# b291_rev0.net
KiCad netlist of a schematic drawn in EAGLE
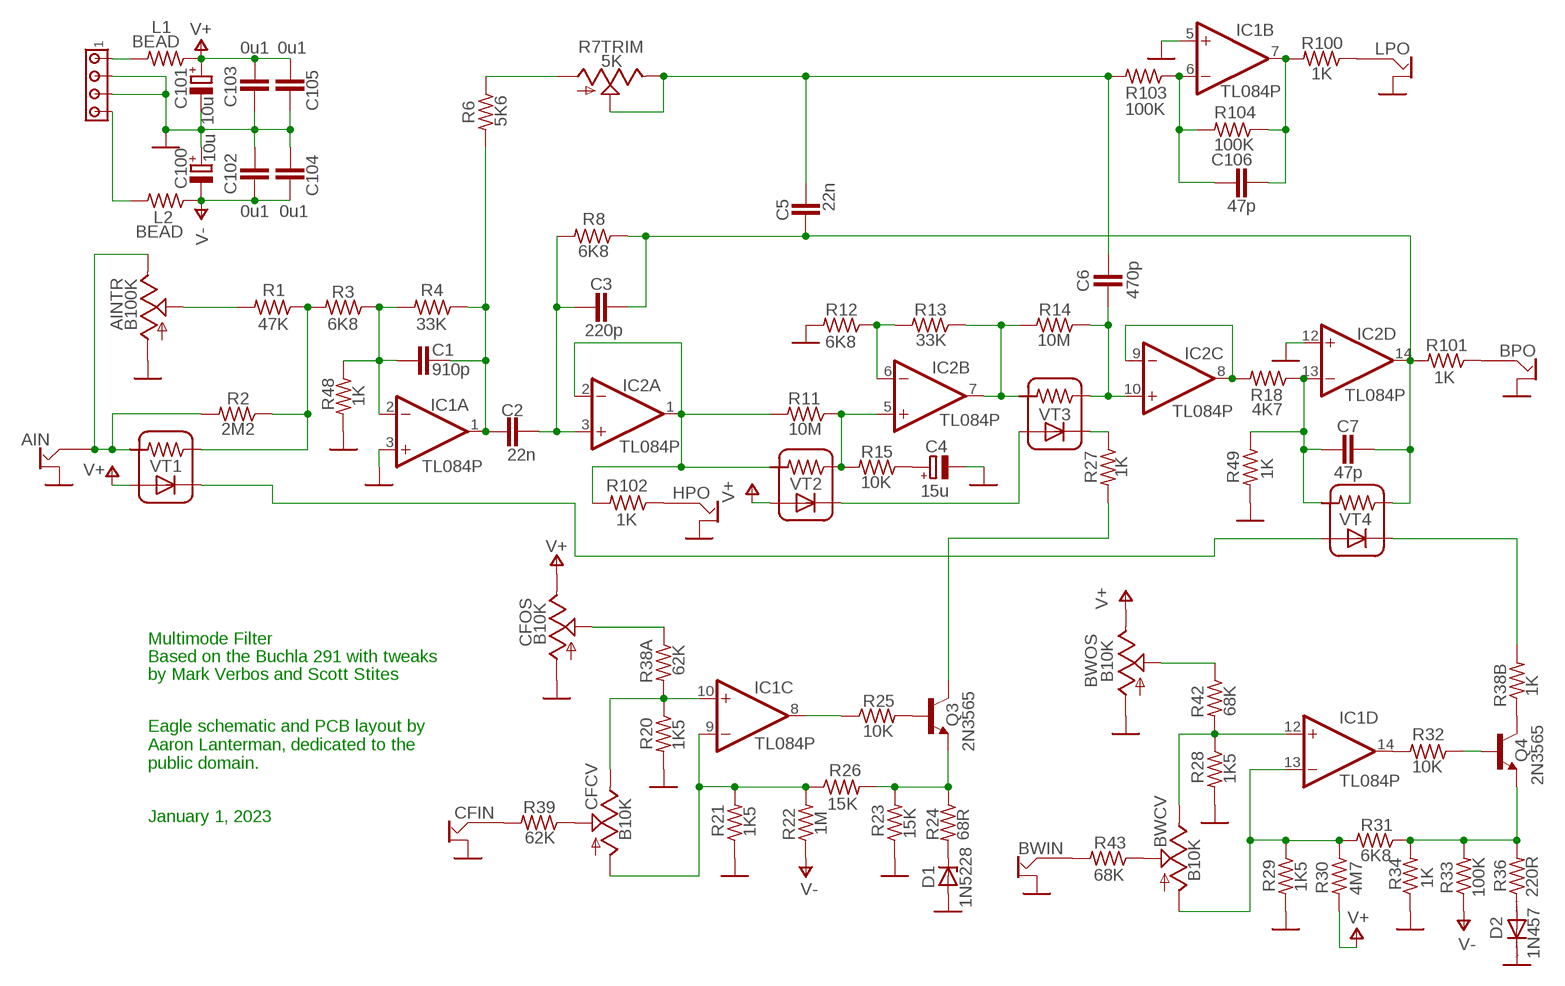
[diagram p0: schematic, sheet 1]

(export (version "E")
  (design (tool "Eeschema 10.0.6"))
  (components
    (comp (ref "AIN")
      (value "OFFBOARD2JACK")
      (footprint "eagle-import:OFFBOARD2JACK")
      (libsource (lib "eagle-import") (part "OFFBOARD2JACK"))
    )
    (comp (ref "AINTR")
      (value "B100K")
      (footprint "eagle-import:B64Y")
      (libsource (lib "eagle-import") (part "TRIM_US-B64Y"))
    )
    (comp (ref "BPO")
      (value "OFFBOARD2JACK")
      (footprint "eagle-import:OFFBOARD2JACK")
      (libsource (lib "eagle-import") (part "OFFBOARD2JACK"))
    )
    (comp (ref "BWCV")
      (value "B10K")
      (footprint "eagle-import:B64Y")
      (libsource (lib "eagle-import") (part "TRIM_US-B64Y"))
    )
    (comp (ref "BWIN")
      (value "OFFBOARD2JACK")
      (footprint "eagle-import:OFFBOARD2JACK")
      (libsource (lib "eagle-import") (part "OFFBOARD2JACK"))
    )
    (comp (ref "BWOS")
      (value "B10K")
      (footprint "eagle-import:B64Y")
      (libsource (lib "eagle-import") (part "TRIM_US-B64Y"))
    )
    (comp (ref "C1")
      (value "910p")
      (footprint "eagle-import:C050-025X075")
      (libsource (lib "eagle-import") (part "C-EU050-025X075"))
    )
    (comp (ref "C2")
      (value "22n")
      (footprint "eagle-import:C050-025X075")
      (libsource (lib "eagle-import") (part "C-EU050-025X075"))
    )
    (comp (ref "C3")
      (value "220p")
      (footprint "eagle-import:C050-025X075")
      (libsource (lib "eagle-import") (part "C-EU050-025X075"))
    )
    (comp (ref "C4")
      (value "15u")
      (footprint "eagle-import:E1,8-4")
      (libsource (lib "eagle-import") (part "CPOL-EUE1.8-4"))
    )
    (comp (ref "C5")
      (value "22n")
      (footprint "eagle-import:C050-025X075")
      (libsource (lib "eagle-import") (part "C-EU050-025X075"))
    )
    (comp (ref "C6")
      (value "470p")
      (footprint "eagle-import:C050-025X075")
      (libsource (lib "eagle-import") (part "C-EU050-025X075"))
    )
    (comp (ref "C7")
      (value "47p")
      (footprint "eagle-import:C050-025X075")
      (libsource (lib "eagle-import") (part "C-EU050-025X075"))
    )
    (comp (ref "C100")
      (value "10u")
      (footprint "eagle-import:E1,8-4")
      (libsource (lib "eagle-import") (part "CPOL-EUE1.8-4"))
    )
    (comp (ref "C101")
      (value "10u")
      (footprint "eagle-import:E1,8-4")
      (libsource (lib "eagle-import") (part "CPOL-EUE1.8-4"))
    )
    (comp (ref "C102")
      (value "0u1")
      (footprint "eagle-import:C050-025X075")
      (libsource (lib "eagle-import") (part "C-EU050-025X075"))
    )
    (comp (ref "C103")
      (value "0u1")
      (footprint "eagle-import:C050-025X075")
      (libsource (lib "eagle-import") (part "C-EU050-025X075"))
    )
    (comp (ref "C104")
      (value "0u1")
      (footprint "eagle-import:C050-025X075")
      (libsource (lib "eagle-import") (part "C-EU050-025X075"))
    )
    (comp (ref "C105")
      (value "0u1")
      (footprint "eagle-import:C050-025X075")
      (libsource (lib "eagle-import") (part "C-EU050-025X075"))
    )
    (comp (ref "C106")
      (value "47p")
      (footprint "eagle-import:C050-025X075")
      (libsource (lib "eagle-import") (part "C-EU050-025X075"))
    )
    (comp (ref "CFCV")
      (value "B10K")
      (footprint "eagle-import:B64Y")
      (libsource (lib "eagle-import") (part "TRIM_US-B64Y"))
    )
    (comp (ref "CFIN")
      (value "OFFBOARD2JACK")
      (footprint "eagle-import:OFFBOARD2JACK")
      (libsource (lib "eagle-import") (part "OFFBOARD2JACK"))
    )
    (comp (ref "CFOS")
      (value "B10K")
      (footprint "eagle-import:B64Y")
      (libsource (lib "eagle-import") (part "TRIM_US-B64Y"))
    )
    (comp (ref "D1")
      (value "1N5228")
      (footprint "eagle-import:DO35Z10")
      (libsource (lib "eagle-import") (part "ZENER-DIODEDO35Z10"))
    )
    (comp (ref "D2")
      (value "1N457")
      (footprint "eagle-import:DO35-7")
      (libsource (lib "eagle-import") (part "1N4148DO35-7"))
    )
    (comp (ref "HPO")
      (value "OFFBOARD2JACK")
      (footprint "eagle-import:OFFBOARD2JACK")
      (libsource (lib "eagle-import") (part "OFFBOARD2JACK"))
    )
    (comp (ref "IC1")
      (value "TL084P")
      (footprint "eagle-import:DIL14")
      (libsource (lib "eagle-import") (part "TL084P"))
    )
    (comp (ref "IC2")
      (value "TL084P")
      (footprint "eagle-import:DIL14")
      (libsource (lib "eagle-import") (part "TL084P"))
    )
    (comp (ref "J1")
      (value "MTA04-156")
      (footprint "eagle-import:1X4MTA")
      (libsource (lib "eagle-import") (part "MTA04-156"))
    )
    (comp (ref "L1")
      (value "BEAD")
      (footprint "eagle-import:0309_10")
      (libsource (lib "eagle-import") (part "R-US_0309/10"))
    )
    (comp (ref "L2")
      (value "BEAD")
      (footprint "eagle-import:0309_10")
      (libsource (lib "eagle-import") (part "R-US_0309/10"))
    )
    (comp (ref "LPO")
      (value "OFFBOARD2JACK")
      (footprint "eagle-import:OFFBOARD2JACK")
      (libsource (lib "eagle-import") (part "OFFBOARD2JACK"))
    )
    (comp (ref "Q3")
      (value "2N3565")
      (footprint "eagle-import:TO92")
      (libsource (lib "eagle-import") (part "2N3565"))
    )
    (comp (ref "Q4")
      (value "2N3565")
      (footprint "eagle-import:TO92")
      (libsource (lib "eagle-import") (part "2N3565"))
    )
    (comp (ref "R1")
      (value "47K")
      (footprint "eagle-import:0207_10")
      (libsource (lib "eagle-import") (part "R-US_0207/10"))
    )
    (comp (ref "R2")
      (value "2M2")
      (footprint "eagle-import:0207_10")
      (libsource (lib "eagle-import") (part "R-US_0207/10"))
    )
    (comp (ref "R3")
      (value "6K8")
      (footprint "eagle-import:0207_10")
      (libsource (lib "eagle-import") (part "R-US_0207/10"))
    )
    (comp (ref "R4")
      (value "33K")
      (footprint "eagle-import:0207_10")
      (libsource (lib "eagle-import") (part "R-US_0207/10"))
    )
    (comp (ref "R6")
      (value "5K6")
      (footprint "eagle-import:0207_10")
      (libsource (lib "eagle-import") (part "R-US_0207/10"))
    )
    (comp (ref "R7TRIM")
      (value "5K")
      (footprint "eagle-import:B64Y")
      (libsource (lib "eagle-import") (part "TRIM_US-B64Y"))
    )
    (comp (ref "R8")
      (value "6K8")
      (footprint "eagle-import:0207_10")
      (libsource (lib "eagle-import") (part "R-US_0207/10"))
    )
    (comp (ref "R11")
      (value "10M")
      (footprint "eagle-import:0207_10")
      (libsource (lib "eagle-import") (part "R-US_0207/10"))
    )
    (comp (ref "R12")
      (value "6K8")
      (footprint "eagle-import:0207_10")
      (libsource (lib "eagle-import") (part "R-US_0207/10"))
    )
    (comp (ref "R13")
      (value "33K")
      (footprint "eagle-import:0207_10")
      (libsource (lib "eagle-import") (part "R-US_0207/10"))
    )
    (comp (ref "R14")
      (value "10M")
      (footprint "eagle-import:0207_10")
      (libsource (lib "eagle-import") (part "R-US_0207/10"))
    )
    (comp (ref "R15")
      (value "10K")
      (footprint "eagle-import:0207_10")
      (libsource (lib "eagle-import") (part "R-US_0207/10"))
    )
    (comp (ref "R18")
      (value "4K7")
      (footprint "eagle-import:0207_10")
      (libsource (lib "eagle-import") (part "R-US_0207/10"))
    )
    (comp (ref "R20")
      (value "1K5")
      (footprint "eagle-import:0207_10")
      (libsource (lib "eagle-import") (part "R-US_0207/10"))
    )
    (comp (ref "R21")
      (value "1K5")
      (footprint "eagle-import:0207_10")
      (libsource (lib "eagle-import") (part "R-US_0207/10"))
    )
    (comp (ref "R22")
      (value "1M")
      (footprint "eagle-import:0207_10")
      (libsource (lib "eagle-import") (part "R-US_0207/10"))
    )
    (comp (ref "R23")
      (value "15K")
      (footprint "eagle-import:0207_10")
      (libsource (lib "eagle-import") (part "R-US_0207/10"))
    )
    (comp (ref "R24")
      (value "68R")
      (footprint "eagle-import:0207_10")
      (libsource (lib "eagle-import") (part "R-US_0207/10"))
    )
    (comp (ref "R25")
      (value "10K")
      (footprint "eagle-import:0207_10")
      (libsource (lib "eagle-import") (part "R-US_0207/10"))
    )
    (comp (ref "R26")
      (value "15K")
      (footprint "eagle-import:0207_10")
      (libsource (lib "eagle-import") (part "R-US_0207/10"))
    )
    (comp (ref "R27")
      (value "1K")
      (footprint "eagle-import:0207_10")
      (libsource (lib "eagle-import") (part "R-US_0207/10"))
    )
    (comp (ref "R28")
      (value "1K5")
      (footprint "eagle-import:0207_10")
      (libsource (lib "eagle-import") (part "R-US_0207/10"))
    )
    (comp (ref "R29")
      (value "1K5")
      (footprint "eagle-import:0207_10")
      (libsource (lib "eagle-import") (part "R-US_0207/10"))
    )
    (comp (ref "R30")
      (value "4M7")
      (footprint "eagle-import:0207_10")
      (libsource (lib "eagle-import") (part "R-US_0207/10"))
    )
    (comp (ref "R31")
      (value "6K8")
      (footprint "eagle-import:0207_10")
      (libsource (lib "eagle-import") (part "R-US_0207/10"))
    )
    (comp (ref "R32")
      (value "10K")
      (footprint "eagle-import:0207_10")
      (libsource (lib "eagle-import") (part "R-US_0207/10"))
    )
    (comp (ref "R33")
      (value "100K")
      (footprint "eagle-import:0207_10")
      (libsource (lib "eagle-import") (part "R-US_0207/10"))
    )
    (comp (ref "R34")
      (value "1K")
      (footprint "eagle-import:0207_10")
      (libsource (lib "eagle-import") (part "R-US_0207/10"))
    )
    (comp (ref "R36")
      (value "220R")
      (footprint "eagle-import:0207_10")
      (libsource (lib "eagle-import") (part "R-US_0207/10"))
    )
    (comp (ref "R38A")
      (value "62K")
      (footprint "eagle-import:0207_10")
      (libsource (lib "eagle-import") (part "R-US_0207/10"))
    )
    (comp (ref "R38B")
      (value "1K")
      (footprint "eagle-import:0207_10")
      (libsource (lib "eagle-import") (part "R-US_0207/10"))
    )
    (comp (ref "R39")
      (value "62K")
      (footprint "eagle-import:0207_10")
      (libsource (lib "eagle-import") (part "R-US_0207/10"))
    )
    (comp (ref "R42")
      (value "68K")
      (footprint "eagle-import:0207_10")
      (libsource (lib "eagle-import") (part "R-US_0207/10"))
    )
    (comp (ref "R43")
      (value "68K")
      (footprint "eagle-import:0207_10")
      (libsource (lib "eagle-import") (part "R-US_0207/10"))
    )
    (comp (ref "R48")
      (value "1K")
      (footprint "eagle-import:0207_10")
      (libsource (lib "eagle-import") (part "R-US_0207/10"))
    )
    (comp (ref "R49")
      (value "1K")
      (footprint "eagle-import:0207_10")
      (libsource (lib "eagle-import") (part "R-US_0207/10"))
    )
    (comp (ref "R100")
      (value "1K")
      (footprint "eagle-import:0207_10")
      (libsource (lib "eagle-import") (part "R-US_0207/10"))
    )
    (comp (ref "R101")
      (value "1K")
      (footprint "eagle-import:0207_10")
      (libsource (lib "eagle-import") (part "R-US_0207/10"))
    )
    (comp (ref "R102")
      (value "1K")
      (footprint "eagle-import:0207_10")
      (libsource (lib "eagle-import") (part "R-US_0207/10"))
    )
    (comp (ref "R103")
      (value "100K")
      (footprint "eagle-import:0207_10")
      (libsource (lib "eagle-import") (part "R-US_0207/10"))
    )
    (comp (ref "R104")
      (value "100K")
      (footprint "eagle-import:0207_10")
      (libsource (lib "eagle-import") (part "R-US_0207/10"))
    )
    (comp (ref "VT1")
      (value "VACTROLSINGLE")
      (footprint "eagle-import:VACTROLSINGLE")
      (libsource (lib "eagle-import") (part "VACTROLSINGLE"))
    )
    (comp (ref "VT2")
      (value "VACTROLSINGLE")
      (footprint "eagle-import:VACTROLSINGLE")
      (libsource (lib "eagle-import") (part "VACTROLSINGLE"))
    )
    (comp (ref "VT3")
      (value "VACTROLSINGLE")
      (footprint "eagle-import:VACTROLSINGLE")
      (libsource (lib "eagle-import") (part "VACTROLSINGLE"))
    )
    (comp (ref "VT4")
      (value "VACTROLSINGLE")
      (footprint "eagle-import:VACTROLSINGLE")
      (libsource (lib "eagle-import") (part "VACTROLSINGLE"))
    )
  )
  (nets
    (net (code "1") (name "GND") (class "Default")
      (node (ref "AIN") (pin "GND") (pinfunction "GND_GND") (pintype "passive"))
      (node (ref "AINTR") (pin "A") (pinfunction "A_A") (pintype "passive"))
      (node (ref "BPO") (pin "GND") (pinfunction "GND_GND") (pintype "passive"))
      (node (ref "BWIN") (pin "GND") (pinfunction "GND_GND") (pintype "passive"))
      (node (ref "BWOS") (pin "A") (pinfunction "A_A") (pintype "passive"))
      (node (ref "C100") (pin "+") (pinfunction "+_+") (pintype "passive"))
      (node (ref "C101") (pin "-") (pinfunction "-_-") (pintype "passive"))
      (node (ref "C102") (pin "1") (pinfunction "1_1") (pintype "passive"))
      (node (ref "C103") (pin "2") (pinfunction "2_2") (pintype "passive"))
      (node (ref "C104") (pin "1") (pinfunction "1_1") (pintype "passive"))
      (node (ref "C105") (pin "2") (pinfunction "2_2") (pintype "passive"))
      (node (ref "C4") (pin "-") (pinfunction "-_-") (pintype "passive"))
      (node (ref "CFIN") (pin "GND") (pinfunction "GND_GND") (pintype "passive"))
      (node (ref "CFOS") (pin "A") (pinfunction "A_A") (pintype "passive"))
      (node (ref "D1") (pin "A") (pinfunction "A_A") (pintype "passive"))
      (node (ref "D2") (pin "C") (pinfunction "C_C") (pintype "passive"))
      (node (ref "HPO") (pin "GND") (pinfunction "GND_GND") (pintype "passive"))
      (node (ref "IC1") (pin "3") (pinfunction "+IN_3") (pintype "input"))
      (node (ref "IC1") (pin "5") (pinfunction "+IN_5") (pintype "input"))
      (node (ref "IC2") (pin "12") (pinfunction "+IN_12") (pintype "input"))
      (node (ref "J1") (pin "2") (pinfunction "2_2") (pintype "passive"))
      (node (ref "J1") (pin "3") (pinfunction "3_3") (pintype "passive"))
      (node (ref "LPO") (pin "GND") (pinfunction "GND_GND") (pintype "passive"))
      (node (ref "R12") (pin "2") (pinfunction "2_2") (pintype "passive"))
      (node (ref "R20") (pin "2") (pinfunction "2_2") (pintype "passive"))
      (node (ref "R21") (pin "1") (pinfunction "1_1") (pintype "passive"))
      (node (ref "R23") (pin "1") (pinfunction "1_1") (pintype "passive"))
      (node (ref "R28") (pin "2") (pinfunction "2_2") (pintype "passive"))
      (node (ref "R29") (pin "2") (pinfunction "2_2") (pintype "passive"))
      (node (ref "R34") (pin "1") (pinfunction "1_1") (pintype "passive"))
      (node (ref "R48") (pin "2") (pinfunction "2_2") (pintype "passive"))
      (node (ref "R49") (pin "2") (pinfunction "2_2") (pintype "passive"))
    )
    (net (code "2") (name "Net-(AINTR-PadS)") (class "Default")
      (node (ref "AINTR") (pin "S") (pinfunction "S_S") (pintype "passive"))
      (node (ref "R1") (pin "2") (pinfunction "2_2") (pintype "passive"))
    )
    (net (code "3") (name "Net-(BPO-PadSIGNAL)") (class "Default")
      (node (ref "BPO") (pin "SIGNAL") (pinfunction "SIGNAL_SIGNAL") (pintype "passive"))
      (node (ref "R101") (pin "1") (pinfunction "1_1") (pintype "passive"))
    )
    (net (code "4") (name "Net-(BWCV-PadS)") (class "Default")
      (node (ref "BWCV") (pin "S") (pinfunction "S_S") (pintype "passive"))
      (node (ref "R43") (pin "1") (pinfunction "1_1") (pintype "passive"))
    )
    (net (code "5") (name "Net-(BWIN-PadSIGNAL)") (class "Default")
      (node (ref "BWIN") (pin "SIGNAL") (pinfunction "SIGNAL_SIGNAL") (pintype "passive"))
      (node (ref "R43") (pin "2") (pinfunction "2_2") (pintype "passive"))
    )
    (net (code "6") (name "Net-(BWOS-PadS)") (class "Default")
      (node (ref "BWOS") (pin "S") (pinfunction "S_S") (pintype "passive"))
      (node (ref "R42") (pin "1") (pinfunction "1_1") (pintype "passive"))
    )
    (net (code "7") (name "Net-(C4-Pad+)") (class "Default")
      (node (ref "C4") (pin "+") (pinfunction "+_+") (pintype "passive"))
      (node (ref "R15") (pin "1") (pinfunction "1_1") (pintype "passive"))
    )
    (net (code "8") (name "Net-(C5-Pad2)") (class "Default")
      (node (ref "C5") (pin "2") (pinfunction "2_2") (pintype "passive"))
      (node (ref "C6") (pin "2") (pinfunction "2_2") (pintype "passive"))
      (node (ref "R103") (pin "2") (pinfunction "2_2") (pintype "passive"))
      (node (ref "R7TRIM") (pin "E") (pinfunction "E_E") (pintype "passive"))
      (node (ref "R7TRIM") (pin "S") (pinfunction "S_S") (pintype "passive"))
    )
    (net (code "9") (name "Net-(CFCV-PadS)") (class "Default")
      (node (ref "CFCV") (pin "S") (pinfunction "S_S") (pintype "passive"))
      (node (ref "R39") (pin "1") (pinfunction "1_1") (pintype "passive"))
    )
    (net (code "10") (name "Net-(CFIN-PadSIGNAL)") (class "Default")
      (node (ref "CFIN") (pin "SIGNAL") (pinfunction "SIGNAL_SIGNAL") (pintype "passive"))
      (node (ref "R39") (pin "2") (pinfunction "2_2") (pintype "passive"))
    )
    (net (code "11") (name "Net-(CFOS-PadS)") (class "Default")
      (node (ref "CFOS") (pin "S") (pinfunction "S_S") (pintype "passive"))
      (node (ref "R38A") (pin "1") (pinfunction "1_1") (pintype "passive"))
    )
    (net (code "12") (name "Net-(D1-PadC)") (class "Default")
      (node (ref "D1") (pin "C") (pinfunction "C_C") (pintype "passive"))
      (node (ref "R24") (pin "2") (pinfunction "2_2") (pintype "passive"))
    )
    (net (code "13") (name "Net-(D2-PadA)") (class "Default")
      (node (ref "D2") (pin "A") (pinfunction "A_A") (pintype "passive"))
      (node (ref "R36") (pin "1") (pinfunction "1_1") (pintype "passive"))
    )
    (net (code "14") (name "Net-(HPO-PadSIGNAL)") (class "Default")
      (node (ref "HPO") (pin "SIGNAL") (pinfunction "SIGNAL_SIGNAL") (pintype "passive"))
      (node (ref "R102") (pin "1") (pinfunction "1_1") (pintype "passive"))
    )
    (net (code "15") (name "Net-(IC1A--IN)") (class "Default")
      (node (ref "C1") (pin "1") (pinfunction "1_1") (pintype "passive"))
      (node (ref "IC1") (pin "2") (pinfunction "-IN_2") (pintype "input"))
      (node (ref "R3") (pin "1") (pinfunction "1_1") (pintype "passive"))
      (node (ref "R4") (pin "2") (pinfunction "2_2") (pintype "passive"))
      (node (ref "R48") (pin "1") (pinfunction "1_1") (pintype "passive"))
    )
    (net (code "16") (name "Net-(IC1A-OUT)") (class "Default")
      (node (ref "C1") (pin "2") (pinfunction "2_2") (pintype "passive"))
      (node (ref "C2") (pin "1") (pinfunction "1_1") (pintype "passive"))
      (node (ref "IC1") (pin "1") (pinfunction "OUT_1") (pintype "output"))
      (node (ref "R4") (pin "1") (pinfunction "1_1") (pintype "passive"))
      (node (ref "R6") (pin "2") (pinfunction "2_2") (pintype "passive"))
    )
    (net (code "17") (name "Net-(IC1B--IN)") (class "Default")
      (node (ref "C106") (pin "1") (pinfunction "1_1") (pintype "passive"))
      (node (ref "IC1") (pin "6") (pinfunction "-IN_6") (pintype "input"))
      (node (ref "R103") (pin "1") (pinfunction "1_1") (pintype "passive"))
      (node (ref "R104") (pin "2") (pinfunction "2_2") (pintype "passive"))
    )
    (net (code "18") (name "Net-(IC1B-OUT)") (class "Default")
      (node (ref "C106") (pin "2") (pinfunction "2_2") (pintype "passive"))
      (node (ref "IC1") (pin "7") (pinfunction "OUT_7") (pintype "output"))
      (node (ref "R100") (pin "2") (pinfunction "2_2") (pintype "passive"))
      (node (ref "R104") (pin "1") (pinfunction "1_1") (pintype "passive"))
    )
    (net (code "19") (name "Net-(IC1C-+IN)") (class "Default")
      (node (ref "CFCV") (pin "E") (pinfunction "E_E") (pintype "passive"))
      (node (ref "IC1") (pin "10") (pinfunction "+IN_10") (pintype "input"))
      (node (ref "R20") (pin "1") (pinfunction "1_1") (pintype "passive"))
      (node (ref "R38A") (pin "2") (pinfunction "2_2") (pintype "passive"))
    )
    (net (code "20") (name "Net-(IC1C--IN)") (class "Default")
      (node (ref "CFCV") (pin "A") (pinfunction "A_A") (pintype "passive"))
      (node (ref "IC1") (pin "9") (pinfunction "-IN_9") (pintype "input"))
      (node (ref "R21") (pin "2") (pinfunction "2_2") (pintype "passive"))
      (node (ref "R22") (pin "2") (pinfunction "2_2") (pintype "passive"))
      (node (ref "R26") (pin "1") (pinfunction "1_1") (pintype "passive"))
    )
    (net (code "21") (name "Net-(IC1C-OUT)") (class "Default")
      (node (ref "IC1") (pin "8") (pinfunction "OUT_8") (pintype "output"))
      (node (ref "R25") (pin "1") (pinfunction "1_1") (pintype "passive"))
    )
    (net (code "22") (name "Net-(IC1D-+IN)") (class "Default")
      (node (ref "BWCV") (pin "E") (pinfunction "E_E") (pintype "passive"))
      (node (ref "IC1") (pin "12") (pinfunction "+IN_12") (pintype "input"))
      (node (ref "R28") (pin "1") (pinfunction "1_1") (pintype "passive"))
      (node (ref "R42") (pin "2") (pinfunction "2_2") (pintype "passive"))
    )
    (net (code "23") (name "Net-(IC1D--IN)") (class "Default")
      (node (ref "BWCV") (pin "A") (pinfunction "A_A") (pintype "passive"))
      (node (ref "IC1") (pin "13") (pinfunction "-IN_13") (pintype "input"))
      (node (ref "R29") (pin "1") (pinfunction "1_1") (pintype "passive"))
      (node (ref "R30") (pin "1") (pinfunction "1_1") (pintype "passive"))
      (node (ref "R31") (pin "2") (pinfunction "2_2") (pintype "passive"))
    )
    (net (code "24") (name "Net-(IC1D-OUT)") (class "Default")
      (node (ref "IC1") (pin "14") (pinfunction "OUT_14") (pintype "output"))
      (node (ref "R32") (pin "2") (pinfunction "2_2") (pintype "passive"))
    )
    (net (code "25") (name "Net-(IC2A-+IN)") (class "Default")
      (node (ref "C2") (pin "2") (pinfunction "2_2") (pintype "passive"))
      (node (ref "C3") (pin "1") (pinfunction "1_1") (pintype "passive"))
      (node (ref "IC2") (pin "3") (pinfunction "+IN_3") (pintype "input"))
      (node (ref "R8") (pin "2") (pinfunction "2_2") (pintype "passive"))
    )
    (net (code "26") (name "Net-(IC2A--IN)") (class "Default")
      (node (ref "IC2") (pin "1") (pinfunction "OUT_1") (pintype "output"))
      (node (ref "IC2") (pin "2") (pinfunction "-IN_2") (pintype "input"))
      (node (ref "R102") (pin "2") (pinfunction "2_2") (pintype "passive"))
      (node (ref "R11") (pin "2") (pinfunction "2_2") (pintype "passive"))
      (node (ref "VT2") (pin "CELLB") (pinfunction "RB_CELLB") (pintype "passive"))
    )
    (net (code "27") (name "Net-(IC2B-+IN)") (class "Default")
      (node (ref "IC2") (pin "5") (pinfunction "+IN_5") (pintype "input"))
      (node (ref "R11") (pin "1") (pinfunction "1_1") (pintype "passive"))
      (node (ref "R15") (pin "2") (pinfunction "2_2") (pintype "passive"))
      (node (ref "VT2") (pin "CELLA") (pinfunction "RA_CELLA") (pintype "passive"))
    )
    (net (code "28") (name "Net-(IC2B--IN)") (class "Default")
      (node (ref "IC2") (pin "6") (pinfunction "-IN_6") (pintype "input"))
      (node (ref "R12") (pin "1") (pinfunction "1_1") (pintype "passive"))
      (node (ref "R13") (pin "2") (pinfunction "2_2") (pintype "passive"))
    )
    (net (code "29") (name "Net-(IC2B-OUT)") (class "Default")
      (node (ref "IC2") (pin "7") (pinfunction "OUT_7") (pintype "output"))
      (node (ref "R13") (pin "1") (pinfunction "1_1") (pintype "passive"))
      (node (ref "R14") (pin "2") (pinfunction "2_2") (pintype "passive"))
      (node (ref "VT3") (pin "CELLB") (pinfunction "RB_CELLB") (pintype "passive"))
    )
    (net (code "30") (name "Net-(IC2C-+IN)") (class "Default")
      (node (ref "C6") (pin "1") (pinfunction "1_1") (pintype "passive"))
      (node (ref "IC2") (pin "10") (pinfunction "+IN_10") (pintype "input"))
      (node (ref "R14") (pin "1") (pinfunction "1_1") (pintype "passive"))
      (node (ref "VT3") (pin "CELLA") (pinfunction "RA_CELLA") (pintype "passive"))
    )
    (net (code "31") (name "Net-(IC2C--IN)") (class "Default")
      (node (ref "IC2") (pin "8") (pinfunction "OUT_8") (pintype "output"))
      (node (ref "IC2") (pin "9") (pinfunction "-IN_9") (pintype "input"))
      (node (ref "R18") (pin "2") (pinfunction "2_2") (pintype "passive"))
    )
    (net (code "32") (name "Net-(IC2D--IN)") (class "Default")
      (node (ref "C7") (pin "1") (pinfunction "1_1") (pintype "passive"))
      (node (ref "IC2") (pin "13") (pinfunction "-IN_13") (pintype "input"))
      (node (ref "R18") (pin "1") (pinfunction "1_1") (pintype "passive"))
      (node (ref "R49") (pin "1") (pinfunction "1_1") (pintype "passive"))
      (node (ref "VT4") (pin "CELLB") (pinfunction "RB_CELLB") (pintype "passive"))
    )
    (net (code "33") (name "Net-(IC2D-OUT)") (class "Default")
      (node (ref "C3") (pin "2") (pinfunction "2_2") (pintype "passive"))
      (node (ref "C5") (pin "1") (pinfunction "1_1") (pintype "passive"))
      (node (ref "C7") (pin "2") (pinfunction "2_2") (pintype "passive"))
      (node (ref "IC2") (pin "14") (pinfunction "OUT_14") (pintype "output"))
      (node (ref "R101") (pin "2") (pinfunction "2_2") (pintype "passive"))
      (node (ref "R8") (pin "1") (pinfunction "1_1") (pintype "passive"))
      (node (ref "VT4") (pin "CELLA") (pinfunction "RA_CELLA") (pintype "passive"))
    )
    (net (code "34") (name "Net-(J1-Pad1)") (class "Default")
      (node (ref "J1") (pin "1") (pinfunction "1_1") (pintype "passive"))
      (node (ref "L1") (pin "2") (pinfunction "2_2") (pintype "passive"))
    )
    (net (code "35") (name "Net-(J1-Pad4)") (class "Default")
      (node (ref "J1") (pin "4") (pinfunction "4_4") (pintype "passive"))
      (node (ref "L2") (pin "2") (pinfunction "2_2") (pintype "passive"))
    )
    (net (code "36") (name "Net-(LPO-PadSIGNAL)") (class "Default")
      (node (ref "LPO") (pin "SIGNAL") (pinfunction "SIGNAL_SIGNAL") (pintype "passive"))
      (node (ref "R100") (pin "1") (pinfunction "1_1") (pintype "passive"))
    )
    (net (code "37") (name "Net-(Q3-B)") (class "Default")
      (node (ref "Q3") (pin "2") (pinfunction "B_2") (pintype "passive"))
      (node (ref "R25") (pin "2") (pinfunction "2_2") (pintype "passive"))
    )
    (net (code "38") (name "Net-(Q3-C)") (class "Default")
      (node (ref "Q3") (pin "1") (pinfunction "C_1") (pintype "passive"))
      (node (ref "R27") (pin "2") (pinfunction "2_2") (pintype "passive"))
    )
    (net (code "39") (name "Net-(Q3-E)") (class "Default")
      (node (ref "Q3") (pin "3") (pinfunction "E_3") (pintype "passive"))
      (node (ref "R23") (pin "2") (pinfunction "2_2") (pintype "passive"))
      (node (ref "R24") (pin "1") (pinfunction "1_1") (pintype "passive"))
      (node (ref "R26") (pin "2") (pinfunction "2_2") (pintype "passive"))
    )
    (net (code "40") (name "Net-(Q4-B)") (class "Default")
      (node (ref "Q4") (pin "2") (pinfunction "B_2") (pintype "passive"))
      (node (ref "R32") (pin "1") (pinfunction "1_1") (pintype "passive"))
    )
    (net (code "41") (name "Net-(Q4-C)") (class "Default")
      (node (ref "Q4") (pin "1") (pinfunction "C_1") (pintype "passive"))
      (node (ref "R38B") (pin "1") (pinfunction "1_1") (pintype "passive"))
    )
    (net (code "42") (name "Net-(Q4-E)") (class "Default")
      (node (ref "Q4") (pin "3") (pinfunction "E_3") (pintype "passive"))
      (node (ref "R31") (pin "1") (pinfunction "1_1") (pintype "passive"))
      (node (ref "R33") (pin "2") (pinfunction "2_2") (pintype "passive"))
      (node (ref "R34") (pin "2") (pinfunction "2_2") (pintype "passive"))
      (node (ref "R36") (pin "2") (pinfunction "2_2") (pintype "passive"))
    )
    (net (code "43") (name "Net-(R6-Pad1)") (class "Default")
      (node (ref "R6") (pin "1") (pinfunction "1_1") (pintype "passive"))
      (node (ref "R7TRIM") (pin "A") (pinfunction "A_A") (pintype "passive"))
    )
    (net (code "44") (name "Net-(R27-Pad1)") (class "Default")
      (node (ref "R27") (pin "1") (pinfunction "1_1") (pintype "passive"))
      (node (ref "VT3") (pin "LED-") (pinfunction "LED-_LED-") (pintype "passive"))
    )
    (net (code "45") (name "Net-(R38B-Pad2)") (class "Default")
      (node (ref "R38B") (pin "2") (pinfunction "2_2") (pintype "passive"))
      (node (ref "VT4") (pin "LED-") (pinfunction "LED-_LED-") (pintype "passive"))
    )
    (net (code "46") (name "Net-(VT1-PadLED-)") (class "Default")
      (node (ref "VT1") (pin "LED-") (pinfunction "LED-_LED-") (pintype "passive"))
      (node (ref "VT4") (pin "LED+") (pinfunction "LED+_LED+") (pintype "passive"))
    )
    (net (code "47") (name "Net-(VT1-RA)") (class "Default")
      (node (ref "R1") (pin "1") (pinfunction "1_1") (pintype "passive"))
      (node (ref "R2") (pin "1") (pinfunction "1_1") (pintype "passive"))
      (node (ref "R3") (pin "2") (pinfunction "2_2") (pintype "passive"))
      (node (ref "VT1") (pin "CELLA") (pinfunction "RA_CELLA") (pintype "passive"))
    )
    (net (code "48") (name "Net-(VT1-RB)") (class "Default")
      (node (ref "AIN") (pin "SIGNAL") (pinfunction "SIGNAL_SIGNAL") (pintype "passive"))
      (node (ref "AINTR") (pin "E") (pinfunction "E_E") (pintype "passive"))
      (node (ref "R2") (pin "2") (pinfunction "2_2") (pintype "passive"))
      (node (ref "VT1") (pin "CELLB") (pinfunction "RB_CELLB") (pintype "passive"))
    )
    (net (code "49") (name "Net-(VT2-PadLED-)") (class "Default")
      (node (ref "VT2") (pin "LED-") (pinfunction "LED-_LED-") (pintype "passive"))
      (node (ref "VT3") (pin "LED+") (pinfunction "LED+_LED+") (pintype "passive"))
    )
    (net (code "50") (name "V+") (class "Default")
      (node (ref "BWOS") (pin "E") (pinfunction "E_E") (pintype "passive"))
      (node (ref "C101") (pin "+") (pinfunction "+_+") (pintype "passive"))
      (node (ref "C103") (pin "1") (pinfunction "1_1") (pintype "passive"))
      (node (ref "C105") (pin "1") (pinfunction "1_1") (pintype "passive"))
      (node (ref "CFOS") (pin "E") (pinfunction "E_E") (pintype "passive"))
      (node (ref "L1") (pin "1") (pinfunction "1_1") (pintype "passive"))
      (node (ref "R30") (pin "2") (pinfunction "2_2") (pintype "passive"))
      (node (ref "VT1") (pin "LED+") (pinfunction "LED+_LED+") (pintype "passive"))
      (node (ref "VT2") (pin "LED+") (pinfunction "LED+_LED+") (pintype "passive"))
    )
    (net (code "51") (name "V-") (class "Default")
      (node (ref "C100") (pin "-") (pinfunction "-_-") (pintype "passive"))
      (node (ref "C102") (pin "2") (pinfunction "2_2") (pintype "passive"))
      (node (ref "C104") (pin "2") (pinfunction "2_2") (pintype "passive"))
      (node (ref "L2") (pin "1") (pinfunction "1_1") (pintype "passive"))
      (node (ref "R22") (pin "1") (pinfunction "1_1") (pintype "passive"))
      (node (ref "R33") (pin "1") (pinfunction "1_1") (pintype "passive"))
    )
  )
)
